# GCC-ECS-0001_1.net
KiCad netlist of a schematic drawn in EAGLE
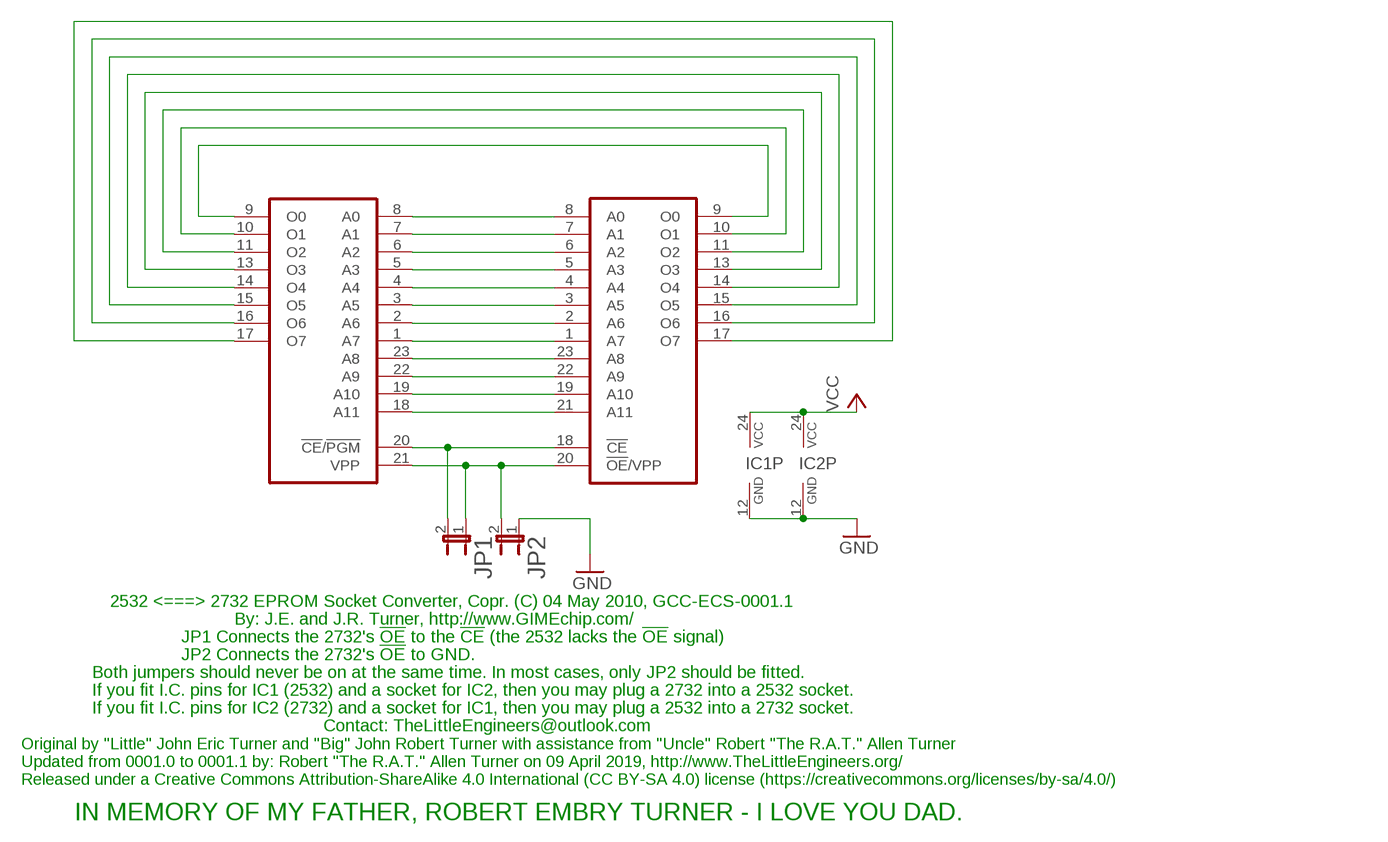
[diagram p0: schematic, sheet 1]

(export (version "E")
  (design (tool "Eeschema 10.0.6"))
  (components
    (comp (ref "IC1")
      (value "2532")
      (footprint "eagle-import:DIL24")
      (libsource (lib "eagle-import") (part "2532"))
    )
    (comp (ref "IC2")
      (value "2732")
      (footprint "eagle-import:DIL24")
      (libsource (lib "eagle-import") (part "2732"))
    )
    (comp (ref "JP1")
      (value "JP")
      (footprint "eagle-import:JP1")
      (libsource (lib "eagle-import") (part "JP"))
    )
    (comp (ref "JP2")
      (value "JP")
      (footprint "eagle-import:JP1")
      (libsource (lib "eagle-import") (part "JP"))
    )
  )
  (nets
    (net (code "1") (name "GND") (class "Default")
      (node (ref "IC1") (pin "12") (pinfunction "GND_12") (pintype "power_in"))
      (node (ref "IC2") (pin "12") (pinfunction "GND_12") (pintype "power_in"))
      (node (ref "JP2") (pin "1") (pinfunction "1_1") (pintype "passive"))
    )
    (net (code "2") (name "Net-(IC1A-A0)") (class "Default")
      (node (ref "IC1") (pin "8") (pinfunction "A0_8") (pintype "input"))
      (node (ref "IC2") (pin "8") (pinfunction "A0_8") (pintype "input"))
    )
    (net (code "3") (name "Net-(IC1A-A1)") (class "Default")
      (node (ref "IC1") (pin "7") (pinfunction "A1_7") (pintype "input"))
      (node (ref "IC2") (pin "7") (pinfunction "A1_7") (pintype "input"))
    )
    (net (code "4") (name "Net-(IC1A-A2)") (class "Default")
      (node (ref "IC1") (pin "6") (pinfunction "A2_6") (pintype "input"))
      (node (ref "IC2") (pin "6") (pinfunction "A2_6") (pintype "input"))
    )
    (net (code "5") (name "Net-(IC1A-A3)") (class "Default")
      (node (ref "IC1") (pin "5") (pinfunction "A3_5") (pintype "input"))
      (node (ref "IC2") (pin "5") (pinfunction "A3_5") (pintype "input"))
    )
    (net (code "6") (name "Net-(IC1A-A4)") (class "Default")
      (node (ref "IC1") (pin "4") (pinfunction "A4_4") (pintype "input"))
      (node (ref "IC2") (pin "4") (pinfunction "A4_4") (pintype "input"))
    )
    (net (code "7") (name "Net-(IC1A-A5)") (class "Default")
      (node (ref "IC1") (pin "3") (pinfunction "A5_3") (pintype "input"))
      (node (ref "IC2") (pin "3") (pinfunction "A5_3") (pintype "input"))
    )
    (net (code "8") (name "Net-(IC1A-A6)") (class "Default")
      (node (ref "IC1") (pin "2") (pinfunction "A6_2") (pintype "input"))
      (node (ref "IC2") (pin "2") (pinfunction "A6_2") (pintype "input"))
    )
    (net (code "9") (name "Net-(IC1A-A7)") (class "Default")
      (node (ref "IC1") (pin "1") (pinfunction "A7_1") (pintype "input"))
      (node (ref "IC2") (pin "1") (pinfunction "A7_1") (pintype "input"))
    )
    (net (code "10") (name "Net-(IC1A-A8)") (class "Default")
      (node (ref "IC1") (pin "23") (pinfunction "A8_23") (pintype "input"))
      (node (ref "IC2") (pin "23") (pinfunction "A8_23") (pintype "input"))
    )
    (net (code "11") (name "Net-(IC1A-A9)") (class "Default")
      (node (ref "IC1") (pin "22") (pinfunction "A9_22") (pintype "input"))
      (node (ref "IC2") (pin "22") (pinfunction "A9_22") (pintype "input"))
    )
    (net (code "12") (name "Net-(IC1A-A10)") (class "Default")
      (node (ref "IC1") (pin "19") (pinfunction "A10_19") (pintype "input"))
      (node (ref "IC2") (pin "19") (pinfunction "A10_19") (pintype "input"))
    )
    (net (code "13") (name "Net-(IC1A-A11)") (class "Default")
      (node (ref "IC1") (pin "18") (pinfunction "A11_18") (pintype "input"))
      (node (ref "IC2") (pin "21") (pinfunction "A11_21") (pintype "input"))
    )
    (net (code "14") (name "Net-(IC1A-O0)") (class "Default")
      (node (ref "IC1") (pin "9") (pinfunction "O0_9") (pintype "tri_state"))
      (node (ref "IC2") (pin "9") (pinfunction "O0_9") (pintype "tri_state"))
    )
    (net (code "15") (name "Net-(IC1A-O1)") (class "Default")
      (node (ref "IC1") (pin "10") (pinfunction "O1_10") (pintype "tri_state"))
      (node (ref "IC2") (pin "10") (pinfunction "O1_10") (pintype "tri_state"))
    )
    (net (code "16") (name "Net-(IC1A-O2)") (class "Default")
      (node (ref "IC1") (pin "11") (pinfunction "O2_11") (pintype "tri_state"))
      (node (ref "IC2") (pin "11") (pinfunction "O2_11") (pintype "tri_state"))
    )
    (net (code "17") (name "Net-(IC1A-O3)") (class "Default")
      (node (ref "IC1") (pin "13") (pinfunction "O3_13") (pintype "tri_state"))
      (node (ref "IC2") (pin "13") (pinfunction "O3_13") (pintype "tri_state"))
    )
    (net (code "18") (name "Net-(IC1A-O4)") (class "Default")
      (node (ref "IC1") (pin "14") (pinfunction "O4_14") (pintype "tri_state"))
      (node (ref "IC2") (pin "14") (pinfunction "O4_14") (pintype "tri_state"))
    )
    (net (code "19") (name "Net-(IC1A-O5)") (class "Default")
      (node (ref "IC1") (pin "15") (pinfunction "O5_15") (pintype "tri_state"))
      (node (ref "IC2") (pin "15") (pinfunction "O5_15") (pintype "tri_state"))
    )
    (net (code "20") (name "Net-(IC1A-O6)") (class "Default")
      (node (ref "IC1") (pin "16") (pinfunction "O6_16") (pintype "tri_state"))
      (node (ref "IC2") (pin "16") (pinfunction "O6_16") (pintype "tri_state"))
    )
    (net (code "21") (name "Net-(IC1A-O7)") (class "Default")
      (node (ref "IC1") (pin "17") (pinfunction "O7_17") (pintype "tri_state"))
      (node (ref "IC2") (pin "17") (pinfunction "O7_17") (pintype "tri_state"))
    )
    (net (code "22") (name "Net-(IC1A-VPP)") (class "Default")
      (node (ref "IC1") (pin "21") (pinfunction "VPP_21") (pintype "input"))
      (node (ref "IC2") (pin "20") (pinfunction "~{OE}/VPP_20") (pintype "input"))
      (node (ref "JP1") (pin "1") (pinfunction "1_1") (pintype "passive"))
      (node (ref "JP2") (pin "2") (pinfunction "2_2") (pintype "passive"))
    )
    (net (code "23") (name "Net-(IC1A-~{CE}{slash}~{PGM})") (class "Default")
      (node (ref "IC1") (pin "20") (pinfunction "~{CE}/~{PGM}_20") (pintype "input"))
      (node (ref "IC2") (pin "18") (pinfunction "~{CE}_18") (pintype "input"))
      (node (ref "JP1") (pin "2") (pinfunction "2_2") (pintype "passive"))
    )
    (net (code "24") (name "VCC") (class "Default")
      (node (ref "IC1") (pin "24") (pinfunction "VCC_24") (pintype "power_in"))
      (node (ref "IC2") (pin "24") (pinfunction "VCC_24") (pintype "power_in"))
    )
  )
)
